# Schematic_v14.net
KiCad netlist of a schematic drawn in EAGLE
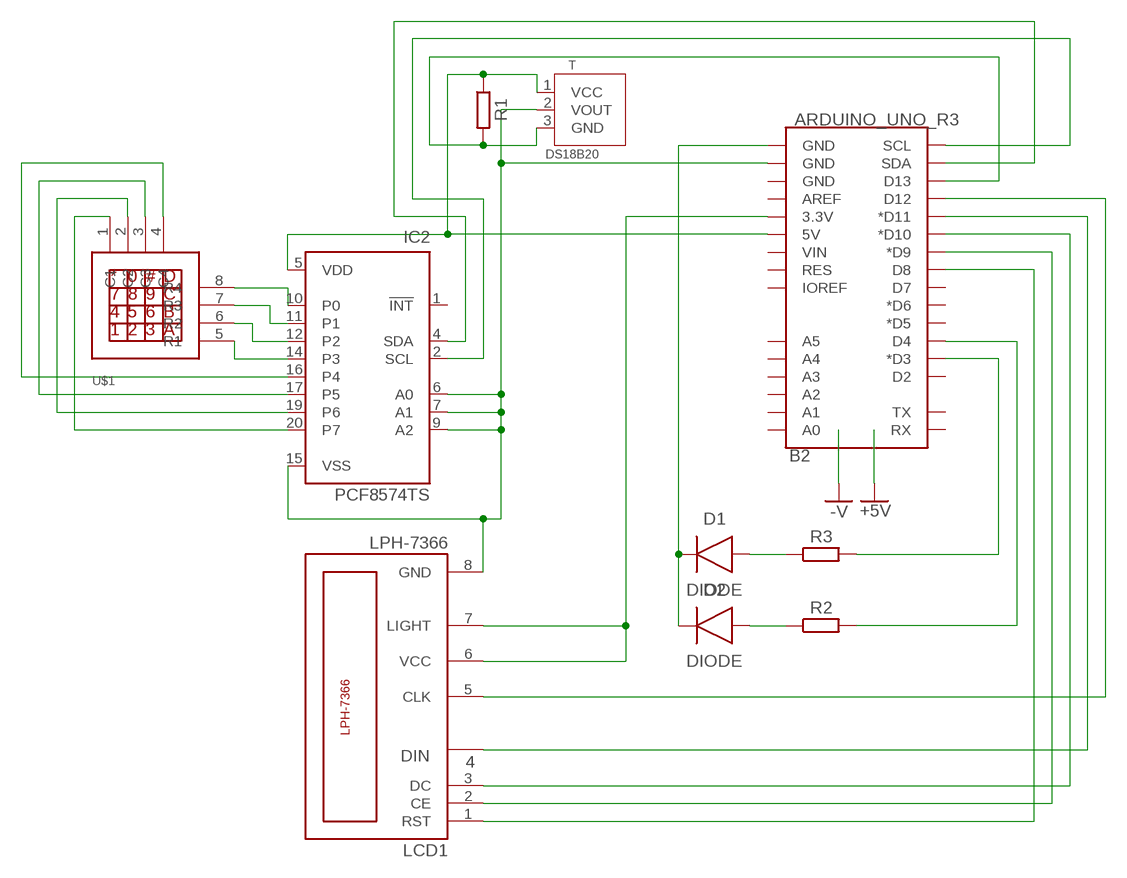
[diagram p0: schematic, sheet 1]

(export (version "E")
  (design (tool "Eeschema 10.0.6"))
  (components
    (comp (ref "B2")
      (value "ARDUINO_UNO_R3")
      (footprint "eagle-import:UNO_R3_SHIELD_NOLABELS_LOCK")
      (libsource (lib "eagle-import") (part "ARDUINO_UNO_R3_SHIELDUNO_R3_SHIELD_NOLABELS_LOCK"))
    )
    (comp (ref "D1")
      (value "DIODE")
      (footprint "eagle-import:DIOM7959X625N")
      (libsource (lib "eagle-import") (part "DIODEDO-214AB(SMC)"))
    )
    (comp (ref "D2")
      (value "DIODE")
      (footprint "eagle-import:DIOM7959X625N")
      (libsource (lib "eagle-import") (part "DIODEDO-214AB(SMC)"))
    )
    (comp (ref "IC2")
      (value "PCF8574TS")
      (footprint "eagle-import:SSOP20")
      (libsource (lib "eagle-import") (part "PCF8574TS"))
    )
    (comp (ref "LCD1")
      (value "LPH-7366")
      (footprint "eagle-import:LPH-7366")
      (libsource (lib "eagle-import") (part "LPH-7366"))
    )
    (comp (ref "R1")
      (value "R_AXIAL-7.2MM-PITCH")
      (footprint "eagle-import:RESAD724W46L381D178B")
      (libsource (lib "eagle-import") (part "RAXIAL-7.2MM-PITCH_"))
    )
    (comp (ref "R2")
      (value "R_AXIAL-7.2MM-PITCH")
      (footprint "eagle-import:RESAD724W46L381D178B")
      (libsource (lib "eagle-import") (part "RAXIAL-7.2MM-PITCH_"))
    )
    (comp (ref "R3")
      (value "R_AXIAL-7.2MM-PITCH")
      (footprint "eagle-import:RESAD724W46L381D178B")
      (libsource (lib "eagle-import") (part "RAXIAL-7.2MM-PITCH_"))
    )
    (comp (ref "T")
      (value "DS18B20")
      (footprint "eagle-import:SOT95P285X113-3N")
      (fields
        (field (name "MANUFACTURER") "Allegro microsystems")
        (field (name "MPN") "A1324LLHLT-T")
        (field (name "MPN_1") "DS18B20")
      )
      (libsource (lib "eagle-import") (part "A1324LLHLT-TLH"))
    )
    (comp (ref "U$1")
      (value "KEYPAD4X4")
      (footprint "eagle-import:KEYPAD4X4")
      (libsource (lib "eagle-import") (part "KEYPAD4X4"))
    )
  )
  (nets
    (net (code "3") (name "Net-(B2-*D3)") (class "Default")
      (node (ref "B2") (pin "D3") (pinfunction "*D3_D3") (pintype "bidirectional"))
      (node (ref "R3") (pin "2") (pinfunction "2_2") (pintype "passive"))
    )
    (net (code "4") (name "Net-(B2-*D9)") (class "Default")
      (node (ref "B2") (pin "D9") (pinfunction "*D9_D9") (pintype "bidirectional"))
      (node (ref "LCD1") (pin "2") (pinfunction "CE_2") (pintype "input"))
    )
    (net (code "5") (name "Net-(B2-*D10)") (class "Default")
      (node (ref "B2") (pin "D10") (pinfunction "*D10_D10") (pintype "bidirectional"))
      (node (ref "LCD1") (pin "3") (pinfunction "DC_3") (pintype "input"))
    )
    (net (code "6") (name "Net-(B2-*D11)") (class "Default")
      (node (ref "B2") (pin "D11") (pinfunction "*D11_D11") (pintype "bidirectional"))
      (node (ref "LCD1") (pin "4") (pinfunction "DIN_4") (pintype "bidirectional"))
    )
    (net (code "7") (name "Net-(B2-PadD4)") (class "Default")
      (node (ref "B2") (pin "D4") (pinfunction "D4_D4") (pintype "bidirectional"))
      (node (ref "R2") (pin "2") (pinfunction "2_2") (pintype "passive"))
    )
    (net (code "8") (name "Net-(D1-A)") (class "Default")
      (node (ref "D1") (pin "2") (pinfunction "A_2") (pintype "passive"))
      (node (ref "R3") (pin "1") (pinfunction "1_1") (pintype "passive"))
    )
    (net (code "9") (name "Net-(D1-C)") (class "Default")
      (node (ref "B2") (pin "GND@0") (pinfunction "GND_GND@0") (pintype "bidirectional"))
      (node (ref "D1") (pin "1") (pinfunction "C_1") (pintype "passive"))
      (node (ref "D2") (pin "1") (pinfunction "C_1") (pintype "passive"))
    )
    (net (code "10") (name "Net-(D2-A)") (class "Default")
      (node (ref "D2") (pin "2") (pinfunction "A_2") (pintype "passive"))
      (node (ref "R2") (pin "1") (pinfunction "1_1") (pintype "passive"))
    )
    (net (code "11") (name "Net-(IC2-A0)") (class "Default")
      (node (ref "B2") (pin "GND@1") (pinfunction "GND_GND@1") (pintype "bidirectional"))
      (node (ref "IC2") (pin "15") (pinfunction "VSS_15") (pintype "power_in"))
      (node (ref "IC2") (pin "6") (pinfunction "A0_6") (pintype "input"))
      (node (ref "IC2") (pin "7") (pinfunction "A1_7") (pintype "input"))
      (node (ref "IC2") (pin "9") (pinfunction "A2_9") (pintype "input"))
      (node (ref "LCD1") (pin "8") (pinfunction "GND_8") (pintype "power_in"))
      (node (ref "T") (pin "2") (pinfunction "VOUT_2") (pintype "output"))
    )
    (net (code "12") (name "Net-(IC2-P0)") (class "Default")
      (node (ref "IC2") (pin "10") (pinfunction "P0_10") (pintype "bidirectional"))
      (node (ref "U$1") (pin "8") (pinfunction "R4_8") (pintype "bidirectional"))
    )
    (net (code "13") (name "Net-(IC2-P1)") (class "Default")
      (node (ref "IC2") (pin "11") (pinfunction "P1_11") (pintype "bidirectional"))
      (node (ref "U$1") (pin "7") (pinfunction "R3_7") (pintype "bidirectional"))
    )
    (net (code "14") (name "Net-(IC2-P2)") (class "Default")
      (node (ref "IC2") (pin "12") (pinfunction "P2_12") (pintype "bidirectional"))
      (node (ref "U$1") (pin "6") (pinfunction "R2_6") (pintype "bidirectional"))
    )
    (net (code "15") (name "Net-(IC2-P3)") (class "Default")
      (node (ref "IC2") (pin "14") (pinfunction "P3_14") (pintype "bidirectional"))
      (node (ref "U$1") (pin "5") (pinfunction "R1_5") (pintype "bidirectional"))
    )
    (net (code "16") (name "Net-(IC2-P4)") (class "Default")
      (node (ref "IC2") (pin "16") (pinfunction "P4_16") (pintype "bidirectional"))
      (node (ref "U$1") (pin "4") (pinfunction "C4_4") (pintype "bidirectional"))
    )
    (net (code "17") (name "Net-(IC2-P5)") (class "Default")
      (node (ref "IC2") (pin "17") (pinfunction "P5_17") (pintype "bidirectional"))
      (node (ref "U$1") (pin "3") (pinfunction "C3_3") (pintype "bidirectional"))
    )
    (net (code "18") (name "Net-(IC2-P6)") (class "Default")
      (node (ref "IC2") (pin "19") (pinfunction "P6_19") (pintype "bidirectional"))
      (node (ref "U$1") (pin "2") (pinfunction "C2_2") (pintype "bidirectional"))
    )
    (net (code "19") (name "Net-(IC2-P7)") (class "Default")
      (node (ref "IC2") (pin "20") (pinfunction "P7_20") (pintype "bidirectional"))
      (node (ref "U$1") (pin "1") (pinfunction "C1_1") (pintype "bidirectional"))
    )
    (net (code "20") (name "Net-(IC2-SCL)") (class "Default")
      (node (ref "B2") (pin "SCL") (pinfunction "SCL_SCL") (pintype "bidirectional"))
      (node (ref "IC2") (pin "2") (pinfunction "SCL_2") (pintype "input"))
    )
    (net (code "21") (name "Net-(IC2-SDA)") (class "Default")
      (node (ref "B2") (pin "SDA") (pinfunction "SDA_SDA") (pintype "bidirectional"))
      (node (ref "IC2") (pin "4") (pinfunction "SDA_4") (pintype "bidirectional"))
    )
    (net (code "22") (name "Net-(IC2-VDD)") (class "Default")
      (node (ref "B2") (pin "5V") (pinfunction "5V_5V") (pintype "bidirectional"))
      (node (ref "IC2") (pin "5") (pinfunction "VDD_5") (pintype "power_in"))
      (node (ref "R1") (pin "1") (pinfunction "1_1") (pintype "passive"))
      (node (ref "T") (pin "1") (pinfunction "VCC_1") (pintype "power_in"))
    )
    (net (code "23") (name "Net-(LCD1-CLK)") (class "Default")
      (node (ref "B2") (pin "D12") (pinfunction "D12_D12") (pintype "bidirectional"))
      (node (ref "LCD1") (pin "5") (pinfunction "CLK_5") (pintype "passive"))
    )
    (net (code "24") (name "Net-(LCD1-LIGHT)") (class "Default")
      (node (ref "B2") (pin "3.3V") (pinfunction "3.3V_3.3V") (pintype "bidirectional"))
      (node (ref "LCD1") (pin "6") (pinfunction "VCC_6") (pintype "power_in"))
      (node (ref "LCD1") (pin "7") (pinfunction "LIGHT_7") (pintype "passive"))
    )
    (net (code "25") (name "Net-(LCD1-RST)") (class "Default")
      (node (ref "B2") (pin "D8") (pinfunction "D8_D8") (pintype "bidirectional"))
      (node (ref "LCD1") (pin "1") (pinfunction "RST_1") (pintype "input"))
    )
    (net (code "26") (name "Net-(T-GND)") (class "Default")
      (node (ref "B2") (pin "D13") (pinfunction "D13_D13") (pintype "bidirectional"))
      (node (ref "R1") (pin "2") (pinfunction "2_2") (pintype "passive"))
      (node (ref "T") (pin "3") (pinfunction "GND_3") (pintype "passive"))
    )
    (net (code "27") (name "unconnected-(B2-*D5-PadD5)") (class "Default")
      (node (ref "B2") (pin "D5") (pinfunction "*D5_D5") (pintype "bidirectional"))
    )
    (net (code "28") (name "unconnected-(B2-*D6-PadD6)") (class "Default")
      (node (ref "B2") (pin "D6") (pinfunction "*D6_D6") (pintype "bidirectional"))
    )
    (net (code "29") (name "unconnected-(B2-GND-PadGND@2)") (class "Default")
      (node (ref "B2") (pin "GND@2") (pinfunction "GND_GND@2") (pintype "bidirectional"))
    )
    (net (code "30") (name "unconnected-(B2-PadA0)") (class "Default")
      (node (ref "B2") (pin "A0") (pinfunction "A0_A0") (pintype "bidirectional"))
    )
    (net (code "31") (name "unconnected-(B2-PadA1)") (class "Default")
      (node (ref "B2") (pin "A1") (pinfunction "A1_A1") (pintype "bidirectional"))
    )
    (net (code "32") (name "unconnected-(B2-PadA2)") (class "Default")
      (node (ref "B2") (pin "A2") (pinfunction "A2_A2") (pintype "bidirectional"))
    )
    (net (code "33") (name "unconnected-(B2-PadA3)") (class "Default")
      (node (ref "B2") (pin "A3") (pinfunction "A3_A3") (pintype "bidirectional"))
    )
    (net (code "34") (name "unconnected-(B2-PadA4)") (class "Default")
      (node (ref "B2") (pin "A4") (pinfunction "A4_A4") (pintype "bidirectional"))
    )
    (net (code "35") (name "unconnected-(B2-PadA5)") (class "Default")
      (node (ref "B2") (pin "A5") (pinfunction "A5_A5") (pintype "bidirectional"))
    )
    (net (code "36") (name "unconnected-(B2-PadAREF)") (class "Default")
      (node (ref "B2") (pin "AREF") (pinfunction "AREF_AREF") (pintype "bidirectional"))
    )
    (net (code "37") (name "unconnected-(B2-PadD2)") (class "Default")
      (node (ref "B2") (pin "D2") (pinfunction "D2_D2") (pintype "bidirectional"))
    )
    (net (code "38") (name "unconnected-(B2-PadD7)") (class "Default")
      (node (ref "B2") (pin "D7") (pinfunction "D7_D7") (pintype "bidirectional"))
    )
    (net (code "39") (name "unconnected-(B2-PadIOREF)") (class "Default")
      (node (ref "B2") (pin "IOREF") (pinfunction "IOREF_IOREF") (pintype "bidirectional"))
    )
    (net (code "40") (name "unconnected-(B2-PadRES)") (class "Default")
      (node (ref "B2") (pin "RES") (pinfunction "RES_RES") (pintype "bidirectional"))
    )
    (net (code "41") (name "unconnected-(B2-PadRX)") (class "Default")
      (node (ref "B2") (pin "RX") (pinfunction "RX_RX") (pintype "bidirectional"))
    )
    (net (code "42") (name "unconnected-(B2-PadTX)") (class "Default")
      (node (ref "B2") (pin "TX") (pinfunction "TX_TX") (pintype "bidirectional"))
    )
    (net (code "43") (name "unconnected-(B2-PadVIN)") (class "Default")
      (node (ref "B2") (pin "VIN") (pinfunction "VIN_VIN") (pintype "bidirectional"))
    )
    (net (code "44") (name "unconnected-(IC2-~{INT}-Pad1)") (class "Default")
      (node (ref "IC2") (pin "1") (pinfunction "~{INT}_1") (pintype "output"))
    )
  )
)
